# sensW5.net
KiCad netlist of a schematic drawn in EAGLE
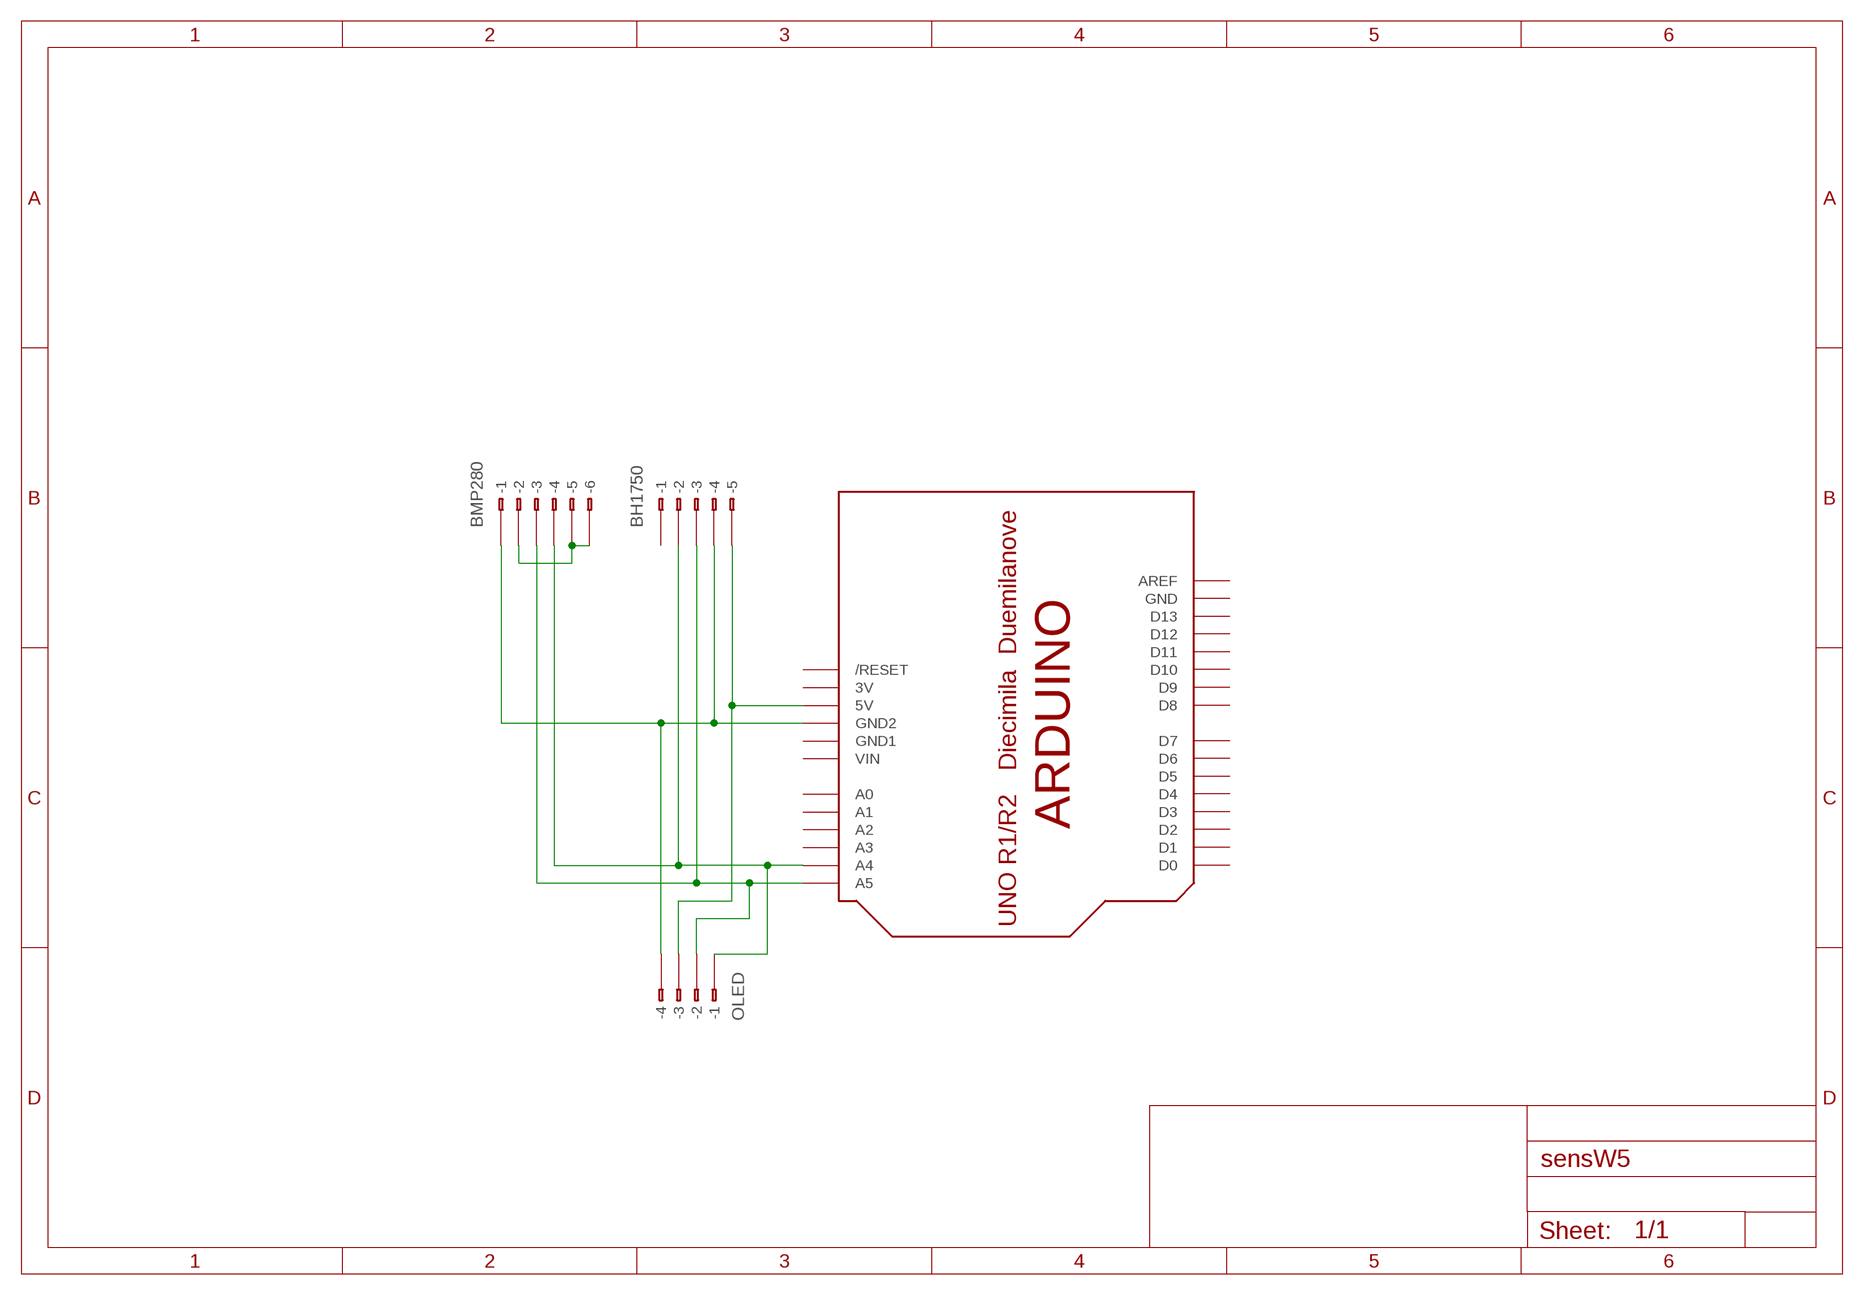
[diagram p0: schematic, sheet 1]

(export (version "E")
  (design (tool "Eeschema 10.0.6"))
  (components
    (comp (ref "BH1750")
      (value "233-105")
      (footprint "eagle-import:233-105")
      (libsource (lib "eagle-import") (part "233-105"))
    )
    (comp (ref "BMP280")
      (value "233-106")
      (footprint "eagle-import:233-106")
      (libsource (lib "eagle-import") (part "233-106"))
    )
    (comp (ref "OLED")
      (value "233-104")
      (footprint "eagle-import:233-104")
      (libsource (lib "eagle-import") (part "233-104"))
    )
    (comp (ref "U$1")
      (value "ARDUINO-NOHOLE")
      (footprint "eagle-import:ARDUINO-NOHOLE")
      (libsource (lib "eagle-import") (part "ARDUINO-NOHOLE"))
    )
  )
  (nets
    (net (code "1") (name "/3V") (class "Default")
      (node (ref "U$1") (pin "3V") (pinfunction "3V_3V") (pintype "power_in"))
    )
    (net (code "2") (name "/GND") (class "Default")
      (node (ref "U$1") (pin "GND") (pinfunction "GND_GND") (pintype "power_in"))
    )
    (net (code "3") (name "/GND1") (class "Default")
      (node (ref "U$1") (pin "GND1") (pinfunction "GND1_GND1") (pintype "power_in"))
    )
    (net (code "4") (name "/VIN") (class "Default")
      (node (ref "U$1") (pin "VIN") (pinfunction "VIN_VIN") (pintype "power_in"))
    )
    (net (code "5") (name "Net-(BH1750-B-2)") (class "Default")
      (node (ref "BH1750") (pin "B2") (pinfunction "B-2_B2") (pintype "passive"))
      (node (ref "BMP280") (pin "B4") (pinfunction "B-4_B4") (pintype "passive"))
      (node (ref "OLED") (pin "B1") (pinfunction "B-1_B1") (pintype "passive"))
      (node (ref "U$1") (pin "A4") (pinfunction "A4_A4") (pintype "bidirectional"))
    )
    (net (code "6") (name "Net-(BH1750-B-3)") (class "Default")
      (node (ref "BH1750") (pin "B3") (pinfunction "B-3_B3") (pintype "passive"))
      (node (ref "BMP280") (pin "B3") (pinfunction "B-3_B3") (pintype "passive"))
      (node (ref "OLED") (pin "B2") (pinfunction "B-2_B2") (pintype "passive"))
      (node (ref "U$1") (pin "A5") (pinfunction "A5_A5") (pintype "bidirectional"))
    )
    (net (code "7") (name "Net-(BH1750-B-4)") (class "Default")
      (node (ref "BH1750") (pin "B4") (pinfunction "B-4_B4") (pintype "passive"))
      (node (ref "BMP280") (pin "B1") (pinfunction "B-1_B1") (pintype "passive"))
      (node (ref "OLED") (pin "B4") (pinfunction "B-4_B4") (pintype "passive"))
      (node (ref "U$1") (pin "GND2") (pinfunction "GND2_GND2") (pintype "power_in"))
    )
    (net (code "8") (name "Net-(BH1750-B-5)") (class "Default")
      (node (ref "BH1750") (pin "B5") (pinfunction "B-5_B5") (pintype "passive"))
      (node (ref "OLED") (pin "B3") (pinfunction "B-3_B3") (pintype "passive"))
      (node (ref "U$1") (pin "5V") (pinfunction "5V_5V") (pintype "power_in"))
    )
    (net (code "9") (name "Net-(BMP280-B-2)") (class "Default")
      (node (ref "BMP280") (pin "B2") (pinfunction "B-2_B2") (pintype "passive"))
      (node (ref "BMP280") (pin "B5") (pinfunction "B-5_B5") (pintype "passive"))
      (node (ref "BMP280") (pin "B6") (pinfunction "B-6_B6") (pintype "passive"))
    )
    (net (code "10") (name "unconnected-(BH1750--1-PadA1)") (class "Default")
      (node (ref "BH1750") (pin "A1") (pinfunction "-1_A1") (pintype "passive"))
    )
    (net (code "11") (name "unconnected-(BH1750--2-PadA2)") (class "Default")
      (node (ref "BH1750") (pin "A2") (pinfunction "-2_A2") (pintype "passive"))
    )
    (net (code "12") (name "unconnected-(BH1750--3-PadA3)") (class "Default")
      (node (ref "BH1750") (pin "A3") (pinfunction "-3_A3") (pintype "passive"))
    )
    (net (code "13") (name "unconnected-(BH1750--4-PadA4)") (class "Default")
      (node (ref "BH1750") (pin "A4") (pinfunction "-4_A4") (pintype "passive"))
    )
    (net (code "14") (name "unconnected-(BH1750--5-PadA5)") (class "Default")
      (node (ref "BH1750") (pin "A5") (pinfunction "-5_A5") (pintype "passive"))
    )
    (net (code "15") (name "unconnected-(BH1750-B-1-PadB1)") (class "Default")
      (node (ref "BH1750") (pin "B1") (pinfunction "B-1_B1") (pintype "passive"))
    )
    (net (code "16") (name "unconnected-(BMP280--1-PadA1)") (class "Default")
      (node (ref "BMP280") (pin "A1") (pinfunction "-1_A1") (pintype "passive"))
    )
    (net (code "17") (name "unconnected-(BMP280--2-PadA2)") (class "Default")
      (node (ref "BMP280") (pin "A2") (pinfunction "-2_A2") (pintype "passive"))
    )
    (net (code "18") (name "unconnected-(BMP280--3-PadA3)") (class "Default")
      (node (ref "BMP280") (pin "A3") (pinfunction "-3_A3") (pintype "passive"))
    )
    (net (code "19") (name "unconnected-(BMP280--4-PadA4)") (class "Default")
      (node (ref "BMP280") (pin "A4") (pinfunction "-4_A4") (pintype "passive"))
    )
    (net (code "20") (name "unconnected-(BMP280--5-PadA5)") (class "Default")
      (node (ref "BMP280") (pin "A5") (pinfunction "-5_A5") (pintype "passive"))
    )
    (net (code "21") (name "unconnected-(BMP280--6-PadA6)") (class "Default")
      (node (ref "BMP280") (pin "A6") (pinfunction "-6_A6") (pintype "passive"))
    )
    (net (code "22") (name "unconnected-(OLED--1-PadA1)") (class "Default")
      (node (ref "OLED") (pin "A1") (pinfunction "-1_A1") (pintype "passive"))
    )
    (net (code "23") (name "unconnected-(OLED--2-PadA2)") (class "Default")
      (node (ref "OLED") (pin "A2") (pinfunction "-2_A2") (pintype "passive"))
    )
    (net (code "24") (name "unconnected-(OLED--3-PadA3)") (class "Default")
      (node (ref "OLED") (pin "A3") (pinfunction "-3_A3") (pintype "passive"))
    )
    (net (code "25") (name "unconnected-(OLED--4-PadA4)") (class "Default")
      (node (ref "OLED") (pin "A4") (pinfunction "-4_A4") (pintype "passive"))
    )
    (net (code "26") (name "unconnected-(U$1-PadA0)") (class "Default")
      (node (ref "U$1") (pin "A0") (pinfunction "A0_A0") (pintype "bidirectional"))
    )
    (net (code "27") (name "unconnected-(U$1-PadA1)") (class "Default")
      (node (ref "U$1") (pin "A1") (pinfunction "A1_A1") (pintype "bidirectional"))
    )
    (net (code "28") (name "unconnected-(U$1-PadA2)") (class "Default")
      (node (ref "U$1") (pin "A2") (pinfunction "A2_A2") (pintype "bidirectional"))
    )
    (net (code "29") (name "unconnected-(U$1-PadA3)") (class "Default")
      (node (ref "U$1") (pin "A3") (pinfunction "A3_A3") (pintype "bidirectional"))
    )
    (net (code "30") (name "unconnected-(U$1-PadAREF)") (class "Default")
      (node (ref "U$1") (pin "AREF") (pinfunction "AREF_AREF") (pintype "bidirectional"))
    )
    (net (code "31") (name "unconnected-(U$1-PadD0)") (class "Default")
      (node (ref "U$1") (pin "D0") (pinfunction "D0_D0") (pintype "bidirectional"))
    )
    (net (code "32") (name "unconnected-(U$1-PadD1)") (class "Default")
      (node (ref "U$1") (pin "D1") (pinfunction "D1_D1") (pintype "bidirectional"))
    )
    (net (code "33") (name "unconnected-(U$1-PadD2)") (class "Default")
      (node (ref "U$1") (pin "D2") (pinfunction "D2_D2") (pintype "bidirectional"))
    )
    (net (code "34") (name "unconnected-(U$1-PadD3)") (class "Default")
      (node (ref "U$1") (pin "D3") (pinfunction "D3_D3") (pintype "bidirectional"))
    )
    (net (code "35") (name "unconnected-(U$1-PadD4)") (class "Default")
      (node (ref "U$1") (pin "D4") (pinfunction "D4_D4") (pintype "bidirectional"))
    )
    (net (code "36") (name "unconnected-(U$1-PadD5)") (class "Default")
      (node (ref "U$1") (pin "D5") (pinfunction "D5_D5") (pintype "bidirectional"))
    )
    (net (code "37") (name "unconnected-(U$1-PadD6)") (class "Default")
      (node (ref "U$1") (pin "D6") (pinfunction "D6_D6") (pintype "bidirectional"))
    )
    (net (code "38") (name "unconnected-(U$1-PadD7)") (class "Default")
      (node (ref "U$1") (pin "D7") (pinfunction "D7_D7") (pintype "bidirectional"))
    )
    (net (code "39") (name "unconnected-(U$1-PadD8)") (class "Default")
      (node (ref "U$1") (pin "D8") (pinfunction "D8_D8") (pintype "bidirectional"))
    )
    (net (code "40") (name "unconnected-(U$1-PadD9)") (class "Default")
      (node (ref "U$1") (pin "D9") (pinfunction "D9_D9") (pintype "bidirectional"))
    )
    (net (code "41") (name "unconnected-(U$1-PadD10)") (class "Default")
      (node (ref "U$1") (pin "D10") (pinfunction "D10_D10") (pintype "bidirectional"))
    )
    (net (code "42") (name "unconnected-(U$1-PadD11)") (class "Default")
      (node (ref "U$1") (pin "D11") (pinfunction "D11_D11") (pintype "bidirectional"))
    )
    (net (code "43") (name "unconnected-(U$1-PadD12)") (class "Default")
      (node (ref "U$1") (pin "D12") (pinfunction "D12_D12") (pintype "bidirectional"))
    )
    (net (code "44") (name "unconnected-(U$1-PadD13)") (class "Default")
      (node (ref "U$1") (pin "D13") (pinfunction "D13_D13") (pintype "bidirectional"))
    )
    (net (code "45") (name "unconnected-(U$1-{slash}RESET-PadRESET)") (class "Default")
      (node (ref "U$1") (pin "RESET") (pinfunction "/RESET_RESET") (pintype "bidirectional"))
    )
  )
)
